# LED-card-1E.net
KiCad netlist of a schematic drawn in EAGLE
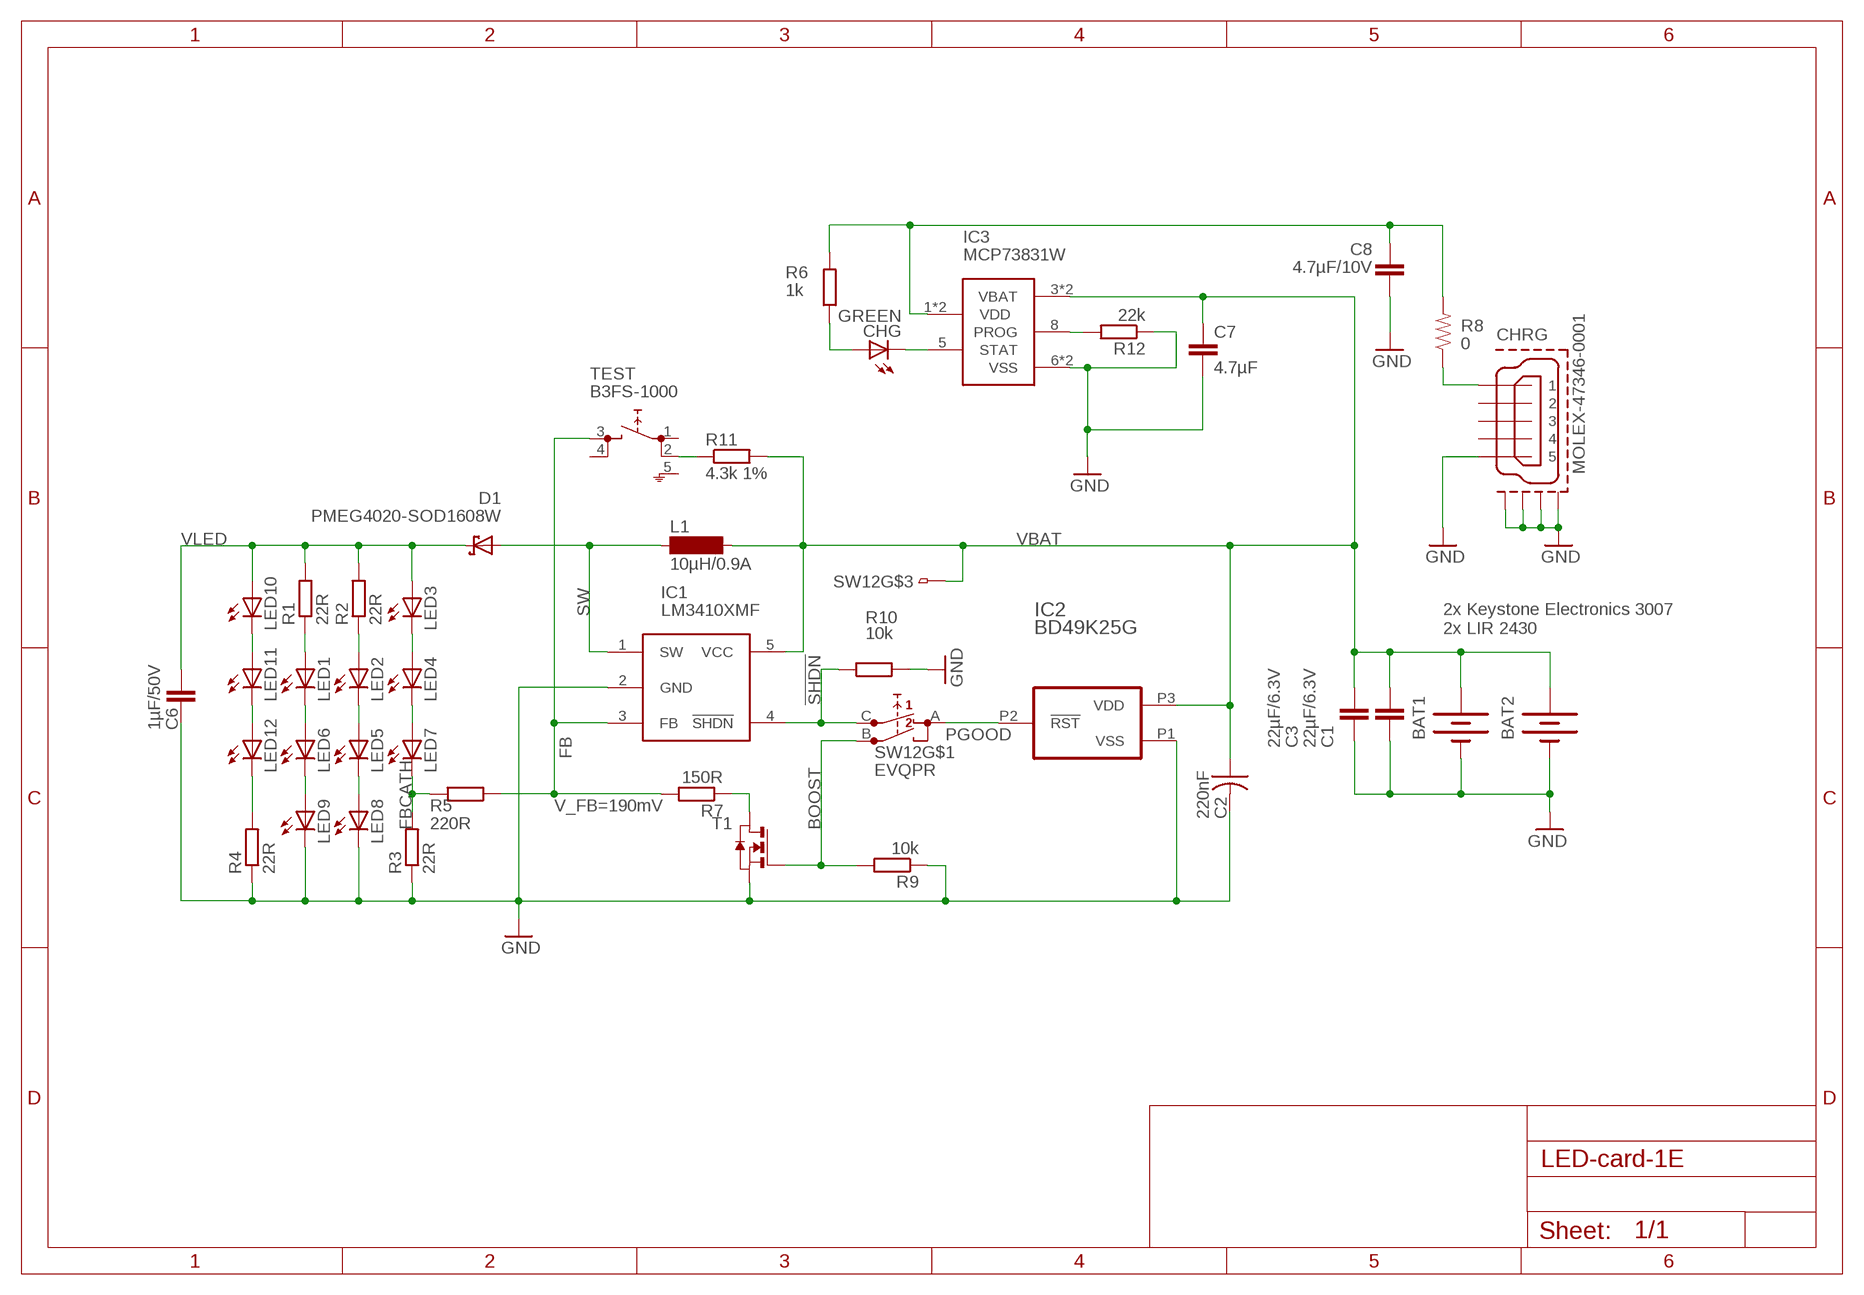
[diagram p0: schematic, sheet 1]

(export (version "E")
  (design (tool "Eeschema 10.0.6"))
  (components
    (comp (ref "BAT1")
      (value "BATTERY")
      (footprint "eagle-import:BATTCON_245MM")
      (fields (field (name "MF") "Keystone Electronics") (field (name "MPN") "3007"))
      (libsource (lib "eagle-import") (part "BATTERY"))
    )
    (comp (ref "BAT2")
      (value "BATTERY")
      (footprint "eagle-import:BATTCON_245MM")
      (fields (field (name "MF") "Keystone Electronics") (field (name "MPN") "3007"))
      (libsource (lib "eagle-import") (part "BATTERY"))
    )
    (comp (ref "C1")
      (value "22µF/6.3V")
      (footprint "eagle-import:C0805K")
      (libsource (lib "eagle-import") (part "C-EUC0805K"))
    )
    (comp (ref "C2")
      (value "220nF")
      (footprint "eagle-import:C0805K")
      (libsource (lib "eagle-import") (part "C-USC0805K"))
    )
    (comp (ref "C3")
      (value "22µF/6.3V")
      (footprint "eagle-import:C0805K")
      (libsource (lib "eagle-import") (part "C-EUC0805K"))
    )
    (comp (ref "C6")
      (value "1µF/50V")
      (footprint "eagle-import:C0805K")
      (libsource (lib "eagle-import") (part "C-EUC0805K"))
    )
    (comp (ref "C7")
      (value "4.7µF")
      (footprint "eagle-import:C0603K")
      (libsource (lib "eagle-import") (part "C-EUC0603K"))
    )
    (comp (ref "C8")
      (value "4.7µF/10V")
      (footprint "eagle-import:C0603K")
      (libsource (lib "eagle-import") (part "C-EUC0603K"))
    )
    (comp (ref "CHG")
      (value "GREEN")
      (footprint "eagle-import:CHIPLED-0603-TTW")
      (libsource (lib "eagle-import") (part "LEDCHIPLED-0603-TTW"))
    )
    (comp (ref "CHRG")
      (value "MOLEX-47346-0001")
      (footprint "eagle-import:MOLEX-47364-0001")
      (libsource (lib "eagle-import") (part "MOLEX-47346-0001"))
    )
    (comp (ref "D1")
      (value "PMEG4020-SOD1608W")
      (footprint "eagle-import:SOD1608W")
      (fields (field (name "MF") "Nexperia"))
      (libsource (lib "eagle-import") (part "PMEG4020-SOD1608W"))
    )
    (comp (ref "IC1")
      (value "LM3410XMF")
      (footprint "eagle-import:SOT23-5L")
      (fields (field (name "MF") "Ti") (field (name "MOUSER") "926-LM3410XMF/NOPB"))
      (libsource (lib "eagle-import") (part "FAN5333"))
    )
    (comp (ref "IC2")
      (value "BD49K25G")
      (footprint "eagle-import:SOT-23")
      (libsource (lib "eagle-import") (part "BD49KG"))
    )
    (comp (ref "IC3")
      (value "MCP73831W")
      (footprint "eagle-import:DFN8W")
      (libsource (lib "eagle-import") (part "MCP73831W"))
    )
    (comp (ref "L1")
      (value "10µH/0.9A")
      (footprint "eagle-import:MS50")
      (fields (field (name "MF") "Taiyo Yuden") (field (name "MPN") "CBC3225T100KR"))
      (libsource (lib "eagle-import") (part "MS50"))
    )
    (comp (ref "LED1")
      (value "LEDSML1206")
      (footprint "eagle-import:SML1206")
      (fields (field (name "MF") "WE") (field (name "MPN") "158301260"))
      (libsource (lib "eagle-import") (part "LEDSML1206"))
    )
    (comp (ref "LED2")
      (value "LEDSML1206")
      (footprint "eagle-import:SML1206")
      (fields (field (name "MF") "WE") (field (name "MPN") "158301260"))
      (libsource (lib "eagle-import") (part "LEDSML1206"))
    )
    (comp (ref "LED3")
      (value "LEDSML1206")
      (footprint "eagle-import:SML1206")
      (fields (field (name "MF") "WE") (field (name "MPN") "158301260"))
      (libsource (lib "eagle-import") (part "LEDSML1206"))
    )
    (comp (ref "LED4")
      (value "LEDSML1206")
      (footprint "eagle-import:SML1206")
      (fields (field (name "MF") "WE") (field (name "MPN") "158301260"))
      (libsource (lib "eagle-import") (part "LEDSML1206"))
    )
    (comp (ref "LED5")
      (value "LEDSML1206")
      (footprint "eagle-import:SML1206")
      (fields (field (name "MF") "WE") (field (name "MPN") "158301260"))
      (libsource (lib "eagle-import") (part "LEDSML1206"))
    )
    (comp (ref "LED6")
      (value "LEDSML1206")
      (footprint "eagle-import:SML1206")
      (fields (field (name "MF") "WE") (field (name "MPN") "158301260"))
      (libsource (lib "eagle-import") (part "LEDSML1206"))
    )
    (comp (ref "LED7")
      (value "LEDSML1206")
      (footprint "eagle-import:SML1206")
      (fields (field (name "MF") "WE") (field (name "MPN") "158301260"))
      (libsource (lib "eagle-import") (part "LEDSML1206"))
    )
    (comp (ref "LED8")
      (value "LEDSML1206")
      (footprint "eagle-import:SML1206")
      (fields (field (name "MF") "WE") (field (name "MPN") "158301260"))
      (libsource (lib "eagle-import") (part "LEDSML1206"))
    )
    (comp (ref "LED9")
      (value "LEDSML1206")
      (footprint "eagle-import:SML1206")
      (fields (field (name "MF") "WE") (field (name "MPN") "158301260"))
      (libsource (lib "eagle-import") (part "LEDSML1206"))
    )
    (comp (ref "LED10")
      (value "LEDSML1206")
      (footprint "eagle-import:SML1206")
      (fields (field (name "MF") "WE") (field (name "MPN") "158301260"))
      (libsource (lib "eagle-import") (part "LEDSML1206"))
    )
    (comp (ref "LED11")
      (value "LEDSML1206")
      (footprint "eagle-import:SML1206")
      (fields (field (name "MF") "WE") (field (name "MPN") "158301260"))
      (libsource (lib "eagle-import") (part "LEDSML1206"))
    )
    (comp (ref "LED12")
      (value "LEDSML1206")
      (footprint "eagle-import:SML1206")
      (fields (field (name "MF") "WE") (field (name "MPN") "158301260"))
      (libsource (lib "eagle-import") (part "LEDSML1206"))
    )
    (comp (ref "R1")
      (value "22R")
      (footprint "eagle-import:R0805")
      (libsource (lib "eagle-import") (part "R-EU_R0805"))
    )
    (comp (ref "R2")
      (value "22R")
      (footprint "eagle-import:R0805")
      (libsource (lib "eagle-import") (part "R-EU_R0805"))
    )
    (comp (ref "R3")
      (value "22R")
      (footprint "eagle-import:R0805")
      (libsource (lib "eagle-import") (part "R-EU_R0805"))
    )
    (comp (ref "R4")
      (value "22R")
      (footprint "eagle-import:R0805")
      (libsource (lib "eagle-import") (part "R-EU_R0805"))
    )
    (comp (ref "R5")
      (value "220R")
      (footprint "eagle-import:R0603")
      (libsource (lib "eagle-import") (part "R-EU_R0603"))
    )
    (comp (ref "R6")
      (value "1k")
      (footprint "eagle-import:R0603")
      (libsource (lib "eagle-import") (part "R-EU_R0603"))
    )
    (comp (ref "R7")
      (value "150R")
      (footprint "eagle-import:R0603")
      (libsource (lib "eagle-import") (part "R-EU_R0603"))
    )
    (comp (ref "R8")
      (value "0")
      (footprint "eagle-import:0805")
      (libsource (lib "eagle-import") (part "RESISTOR0805-RES"))
    )
    (comp (ref "R9")
      (value "10k")
      (footprint "eagle-import:R0603")
      (libsource (lib "eagle-import") (part "R-EU_R0603"))
    )
    (comp (ref "R10")
      (value "10k")
      (footprint "eagle-import:R0603")
      (libsource (lib "eagle-import") (part "R-EU_R0603"))
    )
    (comp (ref "R11")
      (value "4.3k 1%")
      (footprint "eagle-import:R0603")
      (libsource (lib "eagle-import") (part "R-EU_R0603"))
    )
    (comp (ref "R12")
      (value "22k")
      (footprint "eagle-import:R0603")
      (libsource (lib "eagle-import") (part "R-EU_R0603"))
    )
    (comp (ref "SW12")
      (value "EVQPR")
      (footprint "eagle-import:EVQPR-GND")
      (fields
        (field (name "MF") "PANASONIC")
        (field (name "MF_PARTNO") "EVQ-PRHA09")
        (field (name "MOUSER") "667-EVQ-PRHA09")
      )
      (libsource (lib "eagle-import") (part "EVQPR"))
    )
    (comp (ref "T1")
      (value "NMOSSOT23")
      (footprint "eagle-import:SOT-23")
      (libsource (lib "eagle-import") (part "NMOSSOT23"))
    )
    (comp (ref "TEST")
      (value "B3FS-1000")
      (footprint "eagle-import:SKHMPXE010")
      (fields (field (name "MF") "OMRON"))
      (libsource (lib "eagle-import") (part "SKHMPE010S"))
    )
  )
  (nets
    (net (code "1") (name "/BOOST") (class "Default")
      (node (ref "R9") (pin "2") (pinfunction "2_2") (pintype "passive"))
      (node (ref "SW12") (pin "B") (pinfunction "1.2_B") (pintype "passive"))
      (node (ref "T1") (pin "3") (pinfunction "G_3") (pintype "passive"))
    )
    (net (code "2") (name "/FB") (class "Default")
      (node (ref "IC1") (pin "3") (pinfunction "FB_3") (pintype "input"))
      (node (ref "R5") (pin "1") (pinfunction "1_1") (pintype "passive"))
      (node (ref "R7") (pin "2") (pinfunction "2_2") (pintype "passive"))
      (node (ref "TEST") (pin "3") (pinfunction "2.1_3") (pintype "passive"))
    )
    (net (code "3") (name "/FBCATH") (class "Default")
      (node (ref "LED7") (pin "C") (pinfunction "C_C") (pintype "passive"))
      (node (ref "R3") (pin "2") (pinfunction "2_2") (pintype "passive"))
      (node (ref "R5") (pin "2") (pinfunction "2_2") (pintype "passive"))
    )
    (net (code "4") (name "/PGOOD") (class "Default")
      (node (ref "IC2") (pin "P2") (pinfunction "~{RST}_P2") (pintype "input"))
      (node (ref "SW12") (pin "A") (pinfunction "2.1_A") (pintype "passive"))
    )
    (net (code "5") (name "/SW") (class "Default")
      (node (ref "D1") (pin "A") (pinfunction "A_A") (pintype "passive"))
      (node (ref "D1") (pin "A2") (pinfunction "A_A2") (pintype "passive"))
      (node (ref "IC1") (pin "1") (pinfunction "SW_1") (pintype "bidirectional"))
      (node (ref "L1") (pin "1") (pinfunction "1_1") (pintype "passive"))
    )
    (net (code "6") (name "/VBAT") (class "Default")
      (node (ref "BAT1") (pin "1") (pinfunction "+_1") (pintype "power_in"))
      (node (ref "BAT1") (pin "3") (pinfunction "+_3") (pintype "power_in"))
      (node (ref "BAT2") (pin "1") (pinfunction "+_1") (pintype "power_in"))
      (node (ref "BAT2") (pin "3") (pinfunction "+_3") (pintype "power_in"))
      (node (ref "C1") (pin "1") (pinfunction "1_1") (pintype "passive"))
      (node (ref "C2") (pin "1") (pinfunction "1_1") (pintype "passive"))
      (node (ref "C3") (pin "1") (pinfunction "1_1") (pintype "passive"))
      (node (ref "C7") (pin "1") (pinfunction "1_1") (pintype "passive"))
      (node (ref "IC1") (pin "5") (pinfunction "VCC_5") (pintype "power_in"))
      (node (ref "IC2") (pin "P3") (pinfunction "VDD_P3") (pintype "power_in"))
      (node (ref "IC3") (pin "3") (pinfunction "VBAT_3") (pintype "bidirectional"))
      (node (ref "IC3") (pin "4") (pinfunction "VBAT_4") (pintype "bidirectional"))
      (node (ref "L1") (pin "2") (pinfunction "2_2") (pintype "passive"))
      (node (ref "R11") (pin "2") (pinfunction "2_2") (pintype "passive"))
      (node (ref "SW12") (pin "D") (pinfunction "1_D") (pintype "passive"))
    )
    (net (code "7") (name "/VLED") (class "Default")
      (node (ref "C6") (pin "1") (pinfunction "1_1") (pintype "passive"))
      (node (ref "D1") (pin "C") (pinfunction "C_C") (pintype "passive"))
      (node (ref "D1") (pin "C2") (pinfunction "C_C2") (pintype "passive"))
      (node (ref "LED10") (pin "A") (pinfunction "A_A") (pintype "passive"))
      (node (ref "LED3") (pin "A") (pinfunction "A_A") (pintype "passive"))
      (node (ref "R1") (pin "2") (pinfunction "2_2") (pintype "passive"))
      (node (ref "R2") (pin "2") (pinfunction "2_2") (pintype "passive"))
    )
    (net (code "8") (name "/~{SHDN}") (class "Default")
      (node (ref "IC1") (pin "4") (pinfunction "~{SHDN}_4") (pintype "input"))
      (node (ref "R10") (pin "1") (pinfunction "1_1") (pintype "passive"))
      (node (ref "SW12") (pin "C") (pinfunction "1.1_C") (pintype "passive"))
    )
    (net (code "9") (name "GND") (class "Default")
      (node (ref "BAT1") (pin "2") (pinfunction "-_2") (pintype "power_in"))
      (node (ref "BAT2") (pin "2") (pinfunction "-_2") (pintype "power_in"))
      (node (ref "C1") (pin "2") (pinfunction "2_2") (pintype "passive"))
      (node (ref "C2") (pin "2") (pinfunction "2_2") (pintype "passive"))
      (node (ref "C3") (pin "2") (pinfunction "2_2") (pintype "passive"))
      (node (ref "C6") (pin "2") (pinfunction "2_2") (pintype "passive"))
      (node (ref "C7") (pin "2") (pinfunction "2_2") (pintype "passive"))
      (node (ref "C8") (pin "2") (pinfunction "2_2") (pintype "passive"))
      (node (ref "CHRG") (pin "5") (pinfunction "5_5") (pintype "input"))
      (node (ref "CHRG") (pin "GND1") (pinfunction "GND1_GND1") (pintype "bidirectional"))
      (node (ref "CHRG") (pin "GND2") (pinfunction "GND2_GND2") (pintype "bidirectional"))
      (node (ref "CHRG") (pin "GND3") (pinfunction "GND3_GND3") (pintype "bidirectional"))
      (node (ref "CHRG") (pin "GND4") (pinfunction "GND4_GND4") (pintype "bidirectional"))
      (node (ref "IC1") (pin "2") (pinfunction "GND_2") (pintype "power_in"))
      (node (ref "IC2") (pin "P1") (pinfunction "VSS_P1") (pintype "passive"))
      (node (ref "IC3") (pin "6") (pinfunction "VSS_6") (pintype "bidirectional"))
      (node (ref "IC3") (pin "GND") (pinfunction "VSS_GND") (pintype "bidirectional"))
      (node (ref "LED8") (pin "C") (pinfunction "C_C") (pintype "passive"))
      (node (ref "LED9") (pin "C") (pinfunction "C_C") (pintype "passive"))
      (node (ref "R10") (pin "2") (pinfunction "2_2") (pintype "passive"))
      (node (ref "R12") (pin "1") (pinfunction "1_1") (pintype "passive"))
      (node (ref "R3") (pin "1") (pinfunction "1_1") (pintype "passive"))
      (node (ref "R4") (pin "1") (pinfunction "1_1") (pintype "passive"))
      (node (ref "R9") (pin "1") (pinfunction "1_1") (pintype "passive"))
      (node (ref "T1") (pin "2") (pinfunction "S_2") (pintype "passive"))
    )
    (net (code "10") (name "Net-(C8-Pad1)") (class "Default")
      (node (ref "C8") (pin "1") (pinfunction "1_1") (pintype "passive"))
      (node (ref "IC3") (pin "1") (pinfunction "VDD_1") (pintype "bidirectional"))
      (node (ref "IC3") (pin "2") (pinfunction "VDD_2") (pintype "bidirectional"))
      (node (ref "R6") (pin "2") (pinfunction "2_2") (pintype "passive"))
      (node (ref "R8") (pin "2") (pinfunction "2_2") (pintype "passive"))
    )
    (net (code "11") (name "Net-(CHG-A)") (class "Default")
      (node (ref "CHG") (pin "A@1") (pinfunction "A_A@1") (pintype "passive"))
      (node (ref "R6") (pin "1") (pinfunction "1_1") (pintype "passive"))
    )
    (net (code "12") (name "Net-(CHG-C)") (class "Default")
      (node (ref "CHG") (pin "C@1") (pinfunction "C_C@1") (pintype "passive"))
      (node (ref "IC3") (pin "5") (pinfunction "STAT_5") (pintype "bidirectional"))
    )
    (net (code "13") (name "Net-(CHRG-Pad1)") (class "Default")
      (node (ref "CHRG") (pin "1") (pinfunction "1_1") (pintype "input"))
      (node (ref "R8") (pin "1") (pinfunction "1_1") (pintype "passive"))
    )
    (net (code "14") (name "Net-(IC3-PROG)") (class "Default")
      (node (ref "IC3") (pin "8") (pinfunction "PROG_8") (pintype "bidirectional"))
      (node (ref "R12") (pin "2") (pinfunction "2_2") (pintype "passive"))
    )
    (net (code "15") (name "Net-(LED1-PadA)") (class "Default")
      (node (ref "LED1") (pin "A") (pinfunction "A_A") (pintype "passive"))
      (node (ref "R1") (pin "1") (pinfunction "1_1") (pintype "passive"))
    )
    (net (code "16") (name "Net-(LED1-PadC)") (class "Default")
      (node (ref "LED1") (pin "C") (pinfunction "C_C") (pintype "passive"))
      (node (ref "LED6") (pin "A") (pinfunction "A_A") (pintype "passive"))
    )
    (net (code "17") (name "Net-(LED2-PadA)") (class "Default")
      (node (ref "LED2") (pin "A") (pinfunction "A_A") (pintype "passive"))
      (node (ref "R2") (pin "1") (pinfunction "1_1") (pintype "passive"))
    )
    (net (code "18") (name "Net-(LED2-PadC)") (class "Default")
      (node (ref "LED2") (pin "C") (pinfunction "C_C") (pintype "passive"))
      (node (ref "LED5") (pin "A") (pinfunction "A_A") (pintype "passive"))
    )
    (net (code "19") (name "Net-(LED3-PadC)") (class "Default")
      (node (ref "LED3") (pin "C") (pinfunction "C_C") (pintype "passive"))
      (node (ref "LED4") (pin "A") (pinfunction "A_A") (pintype "passive"))
    )
    (net (code "20") (name "Net-(LED4-PadC)") (class "Default")
      (node (ref "LED4") (pin "C") (pinfunction "C_C") (pintype "passive"))
      (node (ref "LED7") (pin "A") (pinfunction "A_A") (pintype "passive"))
    )
    (net (code "21") (name "Net-(LED5-PadC)") (class "Default")
      (node (ref "LED5") (pin "C") (pinfunction "C_C") (pintype "passive"))
      (node (ref "LED8") (pin "A") (pinfunction "A_A") (pintype "passive"))
    )
    (net (code "22") (name "Net-(LED6-PadC)") (class "Default")
      (node (ref "LED6") (pin "C") (pinfunction "C_C") (pintype "passive"))
      (node (ref "LED9") (pin "A") (pinfunction "A_A") (pintype "passive"))
    )
    (net (code "23") (name "Net-(LED10-PadC)") (class "Default")
      (node (ref "LED10") (pin "C") (pinfunction "C_C") (pintype "passive"))
      (node (ref "LED11") (pin "A") (pinfunction "A_A") (pintype "passive"))
    )
    (net (code "24") (name "Net-(LED11-PadC)") (class "Default")
      (node (ref "LED11") (pin "C") (pinfunction "C_C") (pintype "passive"))
      (node (ref "LED12") (pin "A") (pinfunction "A_A") (pintype "passive"))
    )
    (net (code "25") (name "Net-(LED12-PadC)") (class "Default")
      (node (ref "LED12") (pin "C") (pinfunction "C_C") (pintype "passive"))
      (node (ref "R4") (pin "2") (pinfunction "2_2") (pintype "passive"))
    )
    (net (code "26") (name "Net-(T1-D)") (class "Default")
      (node (ref "R7") (pin "1") (pinfunction "1_1") (pintype "passive"))
      (node (ref "T1") (pin "1") (pinfunction "D_1") (pintype "passive"))
    )
    (net (code "27") (name "Net-(TEST-1.2)") (class "Default")
      (node (ref "R11") (pin "1") (pinfunction "1_1") (pintype "passive"))
      (node (ref "TEST") (pin "2") (pinfunction "1.2_2") (pintype "passive"))
    )
    (net (code "28") (name "unconnected-(CHRG-Pad2)") (class "Default")
      (node (ref "CHRG") (pin "2") (pinfunction "2_2") (pintype "input"))
    )
    (net (code "29") (name "unconnected-(CHRG-Pad3)") (class "Default")
      (node (ref "CHRG") (pin "3") (pinfunction "3_3") (pintype "input"))
    )
    (net (code "30") (name "unconnected-(CHRG-Pad4)") (class "Default")
      (node (ref "CHRG") (pin "4") (pinfunction "4_4") (pintype "input"))
    )
    (net (code "31") (name "unconnected-(TEST-1.1-Pad1)") (class "Default")
      (node (ref "TEST") (pin "1") (pinfunction "1.1_1") (pintype "passive"))
    )
    (net (code "32") (name "unconnected-(TEST-2.2-Pad4)") (class "Default")
      (node (ref "TEST") (pin "4") (pinfunction "2.2_4") (pintype "passive"))
    )
    (net (code "33") (name "unconnected-(TEST-SH-Pad5)") (class "Default")
      (node (ref "TEST") (pin "5") (pinfunction "SH_5") (pintype "passive"))
    )
  )
)
